# fpga-bank6.net
KiCad netlist of a schematic drawn in Altium Designer
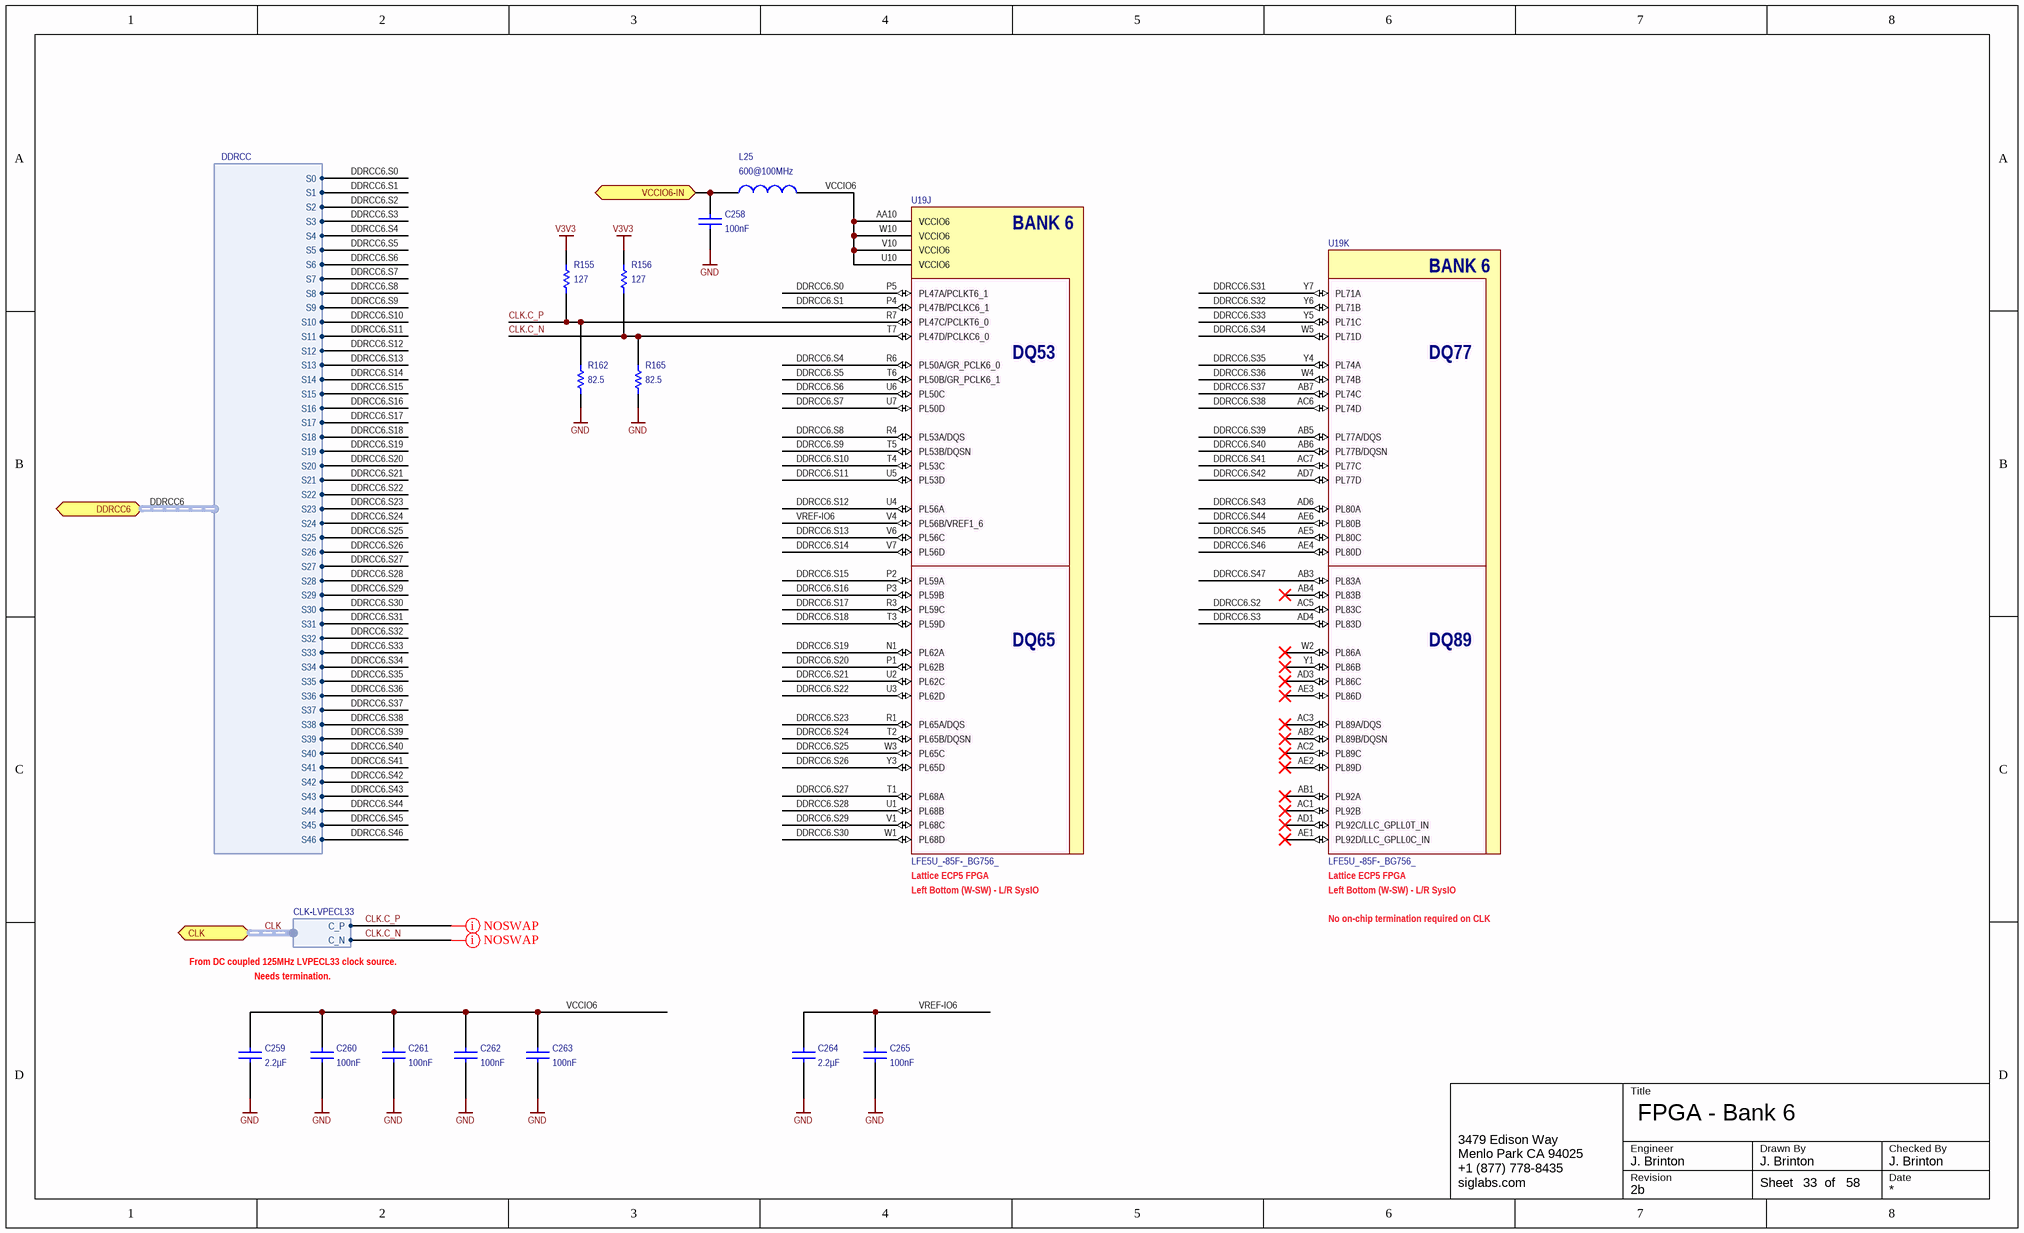
[diagram p0: fpga-bank6.SchDoc]

(export (version "E")
  (design (tool "Eeschema 10.0.6"))
  (components
    (comp (ref "C258")
      (value "100nF")
      (footprint "generic:CAPC1005X56N")
      (description "Ceramic Capacitor 100nF ±10% 16V X7R 0402")
      (fields (field (name "MANUFACTURER") "Murata") (field (name "TOLERANCE") "±10%"))
      (libsource (lib "murata") (part "GRM155R71A104KA01J"))
    )
    (comp (ref "C259")
      (value "2.2µF")
      (footprint "generic:CAPC1608X90N")
      (description "Ceramic Capacitor 2.2uF ±10% 10V X7R 0603")
      (fields (field (name "MANUFACTURER") "Murata") (field (name "TOLERANCE") "±10%"))
      (libsource (lib "murata") (part "GRM188R71A225KE15D"))
    )
    (comp (ref "C260")
      (value "100nF")
      (footprint "generic:CAPC1005X56N")
      (description "Ceramic Capacitor 100nF ±10% 16V X7R 0402")
      (fields (field (name "MANUFACTURER") "Murata") (field (name "TOLERANCE") "±10%"))
      (libsource (lib "murata") (part "GRM155R71A104KA01J"))
    )
    (comp (ref "C261")
      (value "100nF")
      (footprint "generic:CAPC1005X56N")
      (description "Ceramic Capacitor 100nF ±10% 16V X7R 0402")
      (fields (field (name "MANUFACTURER") "Murata") (field (name "TOLERANCE") "±10%"))
      (libsource (lib "murata") (part "GRM155R71A104KA01J"))
    )
    (comp (ref "C262")
      (value "100nF")
      (footprint "generic:CAPC1005X56N")
      (description "Ceramic Capacitor 100nF ±10% 16V X7R 0402")
      (fields (field (name "MANUFACTURER") "Murata") (field (name "TOLERANCE") "±10%"))
      (libsource (lib "murata") (part "GRM155R71A104KA01J"))
    )
    (comp (ref "C263")
      (value "100nF")
      (footprint "generic:CAPC1005X56N")
      (description "Ceramic Capacitor 100nF ±10% 16V X7R 0402")
      (fields (field (name "MANUFACTURER") "Murata") (field (name "TOLERANCE") "±10%"))
      (libsource (lib "murata") (part "GRM155R71A104KA01J"))
    )
    (comp (ref "C264")
      (value "2.2µF")
      (footprint "generic:CAPC1608X90N")
      (description "Ceramic Capacitor 2.2uF ±10% 10V X7R 0603")
      (fields (field (name "MANUFACTURER") "Murata") (field (name "TOLERANCE") "±10%"))
      (libsource (lib "murata") (part "GRM188R71A225KE15D"))
    )
    (comp (ref "C265")
      (value "100nF")
      (footprint "generic:CAPC1005X56N")
      (description "Ceramic Capacitor 100nF ±10% 16V X7R 0402")
      (fields (field (name "MANUFACTURER") "Murata") (field (name "TOLERANCE") "±10%"))
      (libsource (lib "murata") (part "GRM155R71A104KA01J"))
    )
    (comp (ref "L25")
      (value "600@100MHz")
      (footprint "0402")
      (description "Ferrite Bead 600-Ohm @ 100MHz 900mA 0402")
      (fields (field (name "MANUFACTURER") "Murata") (field (name "TOLERANCE") "±25%"))
      (libsource (lib "Graviton") (part "IND 0402"))
    )
    (comp (ref "R155")
      (value "127")
      (footprint "generic:0402")
      (description "Thin Film Resistor 127 ±0.1% 0402")
      (fields (field (name "MANUFACTURER") "Panasonic") (field (name "TOLERANCE") "±0.1%"))
      (libsource (lib "Graviton") (part "RES 0402"))
    )
    (comp (ref "R156")
      (value "127")
      (footprint "generic:0402")
      (description "Thin Film Resistor 127 ±0.1% 0402")
      (fields (field (name "MANUFACTURER") "Panasonic") (field (name "TOLERANCE") "±0.1%"))
      (libsource (lib "Graviton") (part "RES 0402"))
    )
    (comp (ref "R162")
      (value "82.5")
      (footprint "generic:0402")
      (description "Thin Film Resistor 82.5 ±0.1% 0402")
      (fields (field (name "MANUFACTURER") "Panasonic") (field (name "TOLERANCE") "±0.1%"))
      (libsource (lib "Graviton") (part "RES 0402"))
    )
    (comp (ref "R165")
      (value "82.5")
      (footprint "generic:0402")
      (description "Thin Film Resistor 82.5 ±0.1% 0402")
      (fields (field (name "MANUFACTURER") "Panasonic") (field (name "TOLERANCE") "±0.1%"))
      (libsource (lib "Graviton") (part "RES 0402"))
    )
    (comp (ref "U19")
      (value "LFE5U_-85F-_BG756_")
      (footprint "lattice:caBGA756")
      (description "ECP5 FPGA, 85k LUT, 756-caBGA")
      (fields (field (name "MANUFACTURER") "Lattice Semiconductor"))
      (libsource (lib "lattice") (part "LFE5U_-85F-_BG756_"))
    )
  )
  (nets
    (net (code "3") (name "/CLK.C_N") (class "Default")
      (node (ref "R156") (pin "1") (pinfunction "1_1") (pintype "passive"))
      (node (ref "R165") (pin "2") (pinfunction "2_2") (pintype "passive"))
      (node (ref "U19") (pin "T7") (pinfunction "PL47D/PCLKC6_0_T7") (pintype "bidirectional"))
    )
    (net (code "4") (name "/CLK.C_P") (class "Default")
      (node (ref "R155") (pin "1") (pinfunction "1_1") (pintype "passive"))
      (node (ref "R162") (pin "2") (pinfunction "2_2") (pintype "passive"))
      (node (ref "U19") (pin "R7") (pinfunction "PL47C/PCLKT6_0_R7") (pintype "bidirectional"))
    )
    (net (code "6") (name "/DDRCC6.S0") (class "Default")
      (node (ref "U19") (pin "P5") (pinfunction "PL47A/PCLKT6_1_P5") (pintype "bidirectional"))
    )
    (net (code "7") (name "/DDRCC6.S1") (class "Default")
      (node (ref "U19") (pin "P4") (pinfunction "PL47B/PCLKC6_1_P4") (pintype "bidirectional"))
    )
    (net (code "8") (name "/DDRCC6.S2") (class "Default")
      (node (ref "U19") (pin "AC5") (pinfunction "PL83C_AC5") (pintype "bidirectional"))
    )
    (net (code "9") (name "/DDRCC6.S3") (class "Default")
      (node (ref "U19") (pin "AD4") (pinfunction "PL83D_AD4") (pintype "bidirectional"))
    )
    (net (code "10") (name "/DDRCC6.S4") (class "Default")
      (node (ref "U19") (pin "R6") (pinfunction "PL50A/GR_PCLK6_0_R6") (pintype "bidirectional"))
    )
    (net (code "11") (name "/DDRCC6.S5") (class "Default")
      (node (ref "U19") (pin "T6") (pinfunction "PL50B/GR_PCLK6_1_T6") (pintype "bidirectional"))
    )
    (net (code "12") (name "/DDRCC6.S6") (class "Default")
      (node (ref "U19") (pin "U6") (pinfunction "PL50C_U6") (pintype "bidirectional"))
    )
    (net (code "13") (name "/DDRCC6.S7") (class "Default")
      (node (ref "U19") (pin "U7") (pinfunction "PL50D_U7") (pintype "bidirectional"))
    )
    (net (code "14") (name "/DDRCC6.S8") (class "Default")
      (node (ref "U19") (pin "R4") (pinfunction "PL53A/DQS_R4") (pintype "bidirectional"))
    )
    (net (code "15") (name "/DDRCC6.S9") (class "Default")
      (node (ref "U19") (pin "T5") (pinfunction "PL53B/DQSN_T5") (pintype "bidirectional"))
    )
    (net (code "16") (name "/DDRCC6.S10") (class "Default")
      (node (ref "U19") (pin "T4") (pinfunction "PL53C_T4") (pintype "bidirectional"))
    )
    (net (code "17") (name "/DDRCC6.S11") (class "Default")
      (node (ref "U19") (pin "U5") (pinfunction "PL53D_U5") (pintype "bidirectional"))
    )
    (net (code "18") (name "/DDRCC6.S12") (class "Default")
      (node (ref "U19") (pin "U4") (pinfunction "PL56A_U4") (pintype "bidirectional"))
    )
    (net (code "19") (name "/DDRCC6.S13") (class "Default")
      (node (ref "U19") (pin "V6") (pinfunction "PL56C_V6") (pintype "bidirectional"))
    )
    (net (code "20") (name "/DDRCC6.S14") (class "Default")
      (node (ref "U19") (pin "V7") (pinfunction "PL56D_V7") (pintype "bidirectional"))
    )
    (net (code "21") (name "/DDRCC6.S15") (class "Default")
      (node (ref "U19") (pin "P2") (pinfunction "PL59A_P2") (pintype "bidirectional"))
    )
    (net (code "22") (name "/DDRCC6.S16") (class "Default")
      (node (ref "U19") (pin "P3") (pinfunction "PL59B_P3") (pintype "bidirectional"))
    )
    (net (code "23") (name "/DDRCC6.S17") (class "Default")
      (node (ref "U19") (pin "R3") (pinfunction "PL59C_R3") (pintype "bidirectional"))
    )
    (net (code "24") (name "/DDRCC6.S18") (class "Default")
      (node (ref "U19") (pin "T3") (pinfunction "PL59D_T3") (pintype "bidirectional"))
    )
    (net (code "25") (name "/DDRCC6.S19") (class "Default")
      (node (ref "U19") (pin "N1") (pinfunction "PL62A_N1") (pintype "bidirectional"))
    )
    (net (code "26") (name "/DDRCC6.S20") (class "Default")
      (node (ref "U19") (pin "P1") (pinfunction "PL62B_P1") (pintype "bidirectional"))
    )
    (net (code "27") (name "/DDRCC6.S21") (class "Default")
      (node (ref "U19") (pin "U2") (pinfunction "PL62C_U2") (pintype "bidirectional"))
    )
    (net (code "28") (name "/DDRCC6.S22") (class "Default")
      (node (ref "U19") (pin "U3") (pinfunction "PL62D_U3") (pintype "bidirectional"))
    )
    (net (code "29") (name "/DDRCC6.S23") (class "Default")
      (node (ref "U19") (pin "R1") (pinfunction "PL65A/DQS_R1") (pintype "bidirectional"))
    )
    (net (code "30") (name "/DDRCC6.S24") (class "Default")
      (node (ref "U19") (pin "T2") (pinfunction "PL65B/DQSN_T2") (pintype "bidirectional"))
    )
    (net (code "31") (name "/DDRCC6.S25") (class "Default")
      (node (ref "U19") (pin "W3") (pinfunction "PL65C_W3") (pintype "bidirectional"))
    )
    (net (code "32") (name "/DDRCC6.S26") (class "Default")
      (node (ref "U19") (pin "Y3") (pinfunction "PL65D_Y3") (pintype "bidirectional"))
    )
    (net (code "33") (name "/DDRCC6.S27") (class "Default")
      (node (ref "U19") (pin "T1") (pinfunction "PL68A_T1") (pintype "bidirectional"))
    )
    (net (code "34") (name "/DDRCC6.S28") (class "Default")
      (node (ref "U19") (pin "U1") (pinfunction "PL68B_U1") (pintype "bidirectional"))
    )
    (net (code "35") (name "/DDRCC6.S29") (class "Default")
      (node (ref "U19") (pin "V1") (pinfunction "PL68C_V1") (pintype "bidirectional"))
    )
    (net (code "36") (name "/DDRCC6.S30") (class "Default")
      (node (ref "U19") (pin "W1") (pinfunction "PL68D_W1") (pintype "bidirectional"))
    )
    (net (code "37") (name "/DDRCC6.S31") (class "Default")
      (node (ref "U19") (pin "Y7") (pinfunction "PL71A_Y7") (pintype "bidirectional"))
    )
    (net (code "38") (name "/DDRCC6.S32") (class "Default")
      (node (ref "U19") (pin "Y6") (pinfunction "PL71B_Y6") (pintype "bidirectional"))
    )
    (net (code "39") (name "/DDRCC6.S33") (class "Default")
      (node (ref "U19") (pin "Y5") (pinfunction "PL71C_Y5") (pintype "bidirectional"))
    )
    (net (code "40") (name "/DDRCC6.S34") (class "Default")
      (node (ref "U19") (pin "W5") (pinfunction "PL71D_W5") (pintype "bidirectional"))
    )
    (net (code "41") (name "/DDRCC6.S35") (class "Default")
      (node (ref "U19") (pin "Y4") (pinfunction "PL74A_Y4") (pintype "bidirectional"))
    )
    (net (code "42") (name "/DDRCC6.S36") (class "Default")
      (node (ref "U19") (pin "W4") (pinfunction "PL74B_W4") (pintype "bidirectional"))
    )
    (net (code "43") (name "/DDRCC6.S37") (class "Default")
      (node (ref "U19") (pin "AB7") (pinfunction "PL74C_AB7") (pintype "bidirectional"))
    )
    (net (code "44") (name "/DDRCC6.S38") (class "Default")
      (node (ref "U19") (pin "AC6") (pinfunction "PL74D_AC6") (pintype "bidirectional"))
    )
    (net (code "45") (name "/DDRCC6.S39") (class "Default")
      (node (ref "U19") (pin "AB5") (pinfunction "PL77A/DQS_AB5") (pintype "bidirectional"))
    )
    (net (code "46") (name "/DDRCC6.S40") (class "Default")
      (node (ref "U19") (pin "AB6") (pinfunction "PL77B/DQSN_AB6") (pintype "bidirectional"))
    )
    (net (code "47") (name "/DDRCC6.S41") (class "Default")
      (node (ref "U19") (pin "AC7") (pinfunction "PL77C_AC7") (pintype "bidirectional"))
    )
    (net (code "48") (name "/DDRCC6.S42") (class "Default")
      (node (ref "U19") (pin "AD7") (pinfunction "PL77D_AD7") (pintype "bidirectional"))
    )
    (net (code "49") (name "/DDRCC6.S43") (class "Default")
      (node (ref "U19") (pin "AD6") (pinfunction "PL80A_AD6") (pintype "bidirectional"))
    )
    (net (code "50") (name "/DDRCC6.S44") (class "Default")
      (node (ref "U19") (pin "AE6") (pinfunction "PL80B_AE6") (pintype "bidirectional"))
    )
    (net (code "51") (name "/DDRCC6.S45") (class "Default")
      (node (ref "U19") (pin "AE5") (pinfunction "PL80C_AE5") (pintype "bidirectional"))
    )
    (net (code "52") (name "/DDRCC6.S46") (class "Default")
      (node (ref "U19") (pin "AE4") (pinfunction "PL80D_AE4") (pintype "bidirectional"))
    )
    (net (code "53") (name "/DDRCC6.S47") (class "Default")
      (node (ref "U19") (pin "AB3") (pinfunction "PL83A_AB3") (pintype "bidirectional"))
    )
    (net (code "55") (name "/VCCIO6") (class "Default")
      (node (ref "C259") (pin "2") (pinfunction "2_2") (pintype "passive"))
      (node (ref "C260") (pin "2") (pinfunction "2_2") (pintype "passive"))
      (node (ref "C261") (pin "2") (pinfunction "2_2") (pintype "passive"))
      (node (ref "C262") (pin "2") (pinfunction "2_2") (pintype "passive"))
      (node (ref "C263") (pin "2") (pinfunction "2_2") (pintype "passive"))
      (node (ref "L25") (pin "1") (pinfunction "1_1") (pintype "passive"))
      (node (ref "U19") (pin "AA10") (pinfunction "VCCIO6_AA10") (pintype "power_in"))
      (node (ref "U19") (pin "U10") (pinfunction "VCCIO6_U10") (pintype "power_in"))
      (node (ref "U19") (pin "V10") (pinfunction "VCCIO6_V10") (pintype "power_in"))
      (node (ref "U19") (pin "W10") (pinfunction "VCCIO6_W10") (pintype "power_in"))
    )
    (net (code "56") (name "/VCCIO6-IN") (class "Default")
      (node (ref "C258") (pin "2") (pinfunction "2_2") (pintype "passive"))
      (node (ref "L25") (pin "2") (pinfunction "2_2") (pintype "passive"))
    )
    (net (code "57") (name "/VREF-IO6") (class "Default")
      (node (ref "C264") (pin "2") (pinfunction "2_2") (pintype "passive"))
      (node (ref "C265") (pin "2") (pinfunction "2_2") (pintype "passive"))
      (node (ref "U19") (pin "V4") (pinfunction "PL56B/VREF1_6_V4") (pintype "bidirectional"))
    )
    (net (code "58") (name "GND") (class "Default")
      (node (ref "C258") (pin "1") (pinfunction "1_1") (pintype "passive"))
      (node (ref "C259") (pin "1") (pinfunction "1_1") (pintype "passive"))
      (node (ref "C260") (pin "1") (pinfunction "1_1") (pintype "passive"))
      (node (ref "C261") (pin "1") (pinfunction "1_1") (pintype "passive"))
      (node (ref "C262") (pin "1") (pinfunction "1_1") (pintype "passive"))
      (node (ref "C263") (pin "1") (pinfunction "1_1") (pintype "passive"))
      (node (ref "C264") (pin "1") (pinfunction "1_1") (pintype "passive"))
      (node (ref "C265") (pin "1") (pinfunction "1_1") (pintype "passive"))
      (node (ref "R162") (pin "1") (pinfunction "1_1") (pintype "passive"))
      (node (ref "R165") (pin "1") (pinfunction "1_1") (pintype "passive"))
    )
    (net (code "59") (name "V3V3") (class "Default")
      (node (ref "R155") (pin "2") (pinfunction "2_2") (pintype "passive"))
      (node (ref "R156") (pin "2") (pinfunction "2_2") (pintype "passive"))
    )
    (net (code "60") (name "unconnected-(U19K-PL83B-PadAB4)") (class "Default")
      (node (ref "U19") (pin "AB4") (pinfunction "PL83B_AB4") (pintype "bidirectional+no_connect"))
    )
    (net (code "61") (name "unconnected-(U19K-PL86A-PadW2)") (class "Default")
      (node (ref "U19") (pin "W2") (pinfunction "PL86A_W2") (pintype "bidirectional+no_connect"))
    )
    (net (code "62") (name "unconnected-(U19K-PL86B-PadY1)") (class "Default")
      (node (ref "U19") (pin "Y1") (pinfunction "PL86B_Y1") (pintype "bidirectional+no_connect"))
    )
    (net (code "63") (name "unconnected-(U19K-PL86C-PadAD3)") (class "Default")
      (node (ref "U19") (pin "AD3") (pinfunction "PL86C_AD3") (pintype "bidirectional+no_connect"))
    )
    (net (code "64") (name "unconnected-(U19K-PL86D-PadAE3)") (class "Default")
      (node (ref "U19") (pin "AE3") (pinfunction "PL86D_AE3") (pintype "bidirectional+no_connect"))
    )
    (net (code "65") (name "unconnected-(U19K-PL89A{slash}DQS-PadAC3)") (class "Default")
      (node (ref "U19") (pin "AC3") (pinfunction "PL89A/DQS_AC3") (pintype "bidirectional+no_connect"))
    )
    (net (code "66") (name "unconnected-(U19K-PL89B{slash}DQSN-PadAB2)") (class "Default")
      (node (ref "U19") (pin "AB2") (pinfunction "PL89B/DQSN_AB2") (pintype "bidirectional+no_connect"))
    )
    (net (code "67") (name "unconnected-(U19K-PL89C-PadAC2)") (class "Default")
      (node (ref "U19") (pin "AC2") (pinfunction "PL89C_AC2") (pintype "bidirectional+no_connect"))
    )
    (net (code "68") (name "unconnected-(U19K-PL89D-PadAE2)") (class "Default")
      (node (ref "U19") (pin "AE2") (pinfunction "PL89D_AE2") (pintype "bidirectional+no_connect"))
    )
    (net (code "69") (name "unconnected-(U19K-PL92A-PadAB1)") (class "Default")
      (node (ref "U19") (pin "AB1") (pinfunction "PL92A_AB1") (pintype "bidirectional+no_connect"))
    )
    (net (code "70") (name "unconnected-(U19K-PL92B-PadAC1)") (class "Default")
      (node (ref "U19") (pin "AC1") (pinfunction "PL92B_AC1") (pintype "bidirectional+no_connect"))
    )
    (net (code "71") (name "unconnected-(U19K-PL92C{slash}LLC_GPLL0T_IN-PadAD1)") (class "Default")
      (node (ref "U19") (pin "AD1") (pinfunction "PL92C/LLC_GPLL0T_IN_AD1") (pintype "bidirectional+no_connect"))
    )
    (net (code "72") (name "unconnected-(U19K-PL92D{slash}LLC_GPLL0C_IN-PadAE1)") (class "Default")
      (node (ref "U19") (pin "AE1") (pinfunction "PL92D/LLC_GPLL0C_IN_AE1") (pintype "bidirectional+no_connect"))
    )
  )
)
